# openSX70_MEROE_V7-5_20190606B.net
KiCad netlist of a schematic drawn in EAGLE
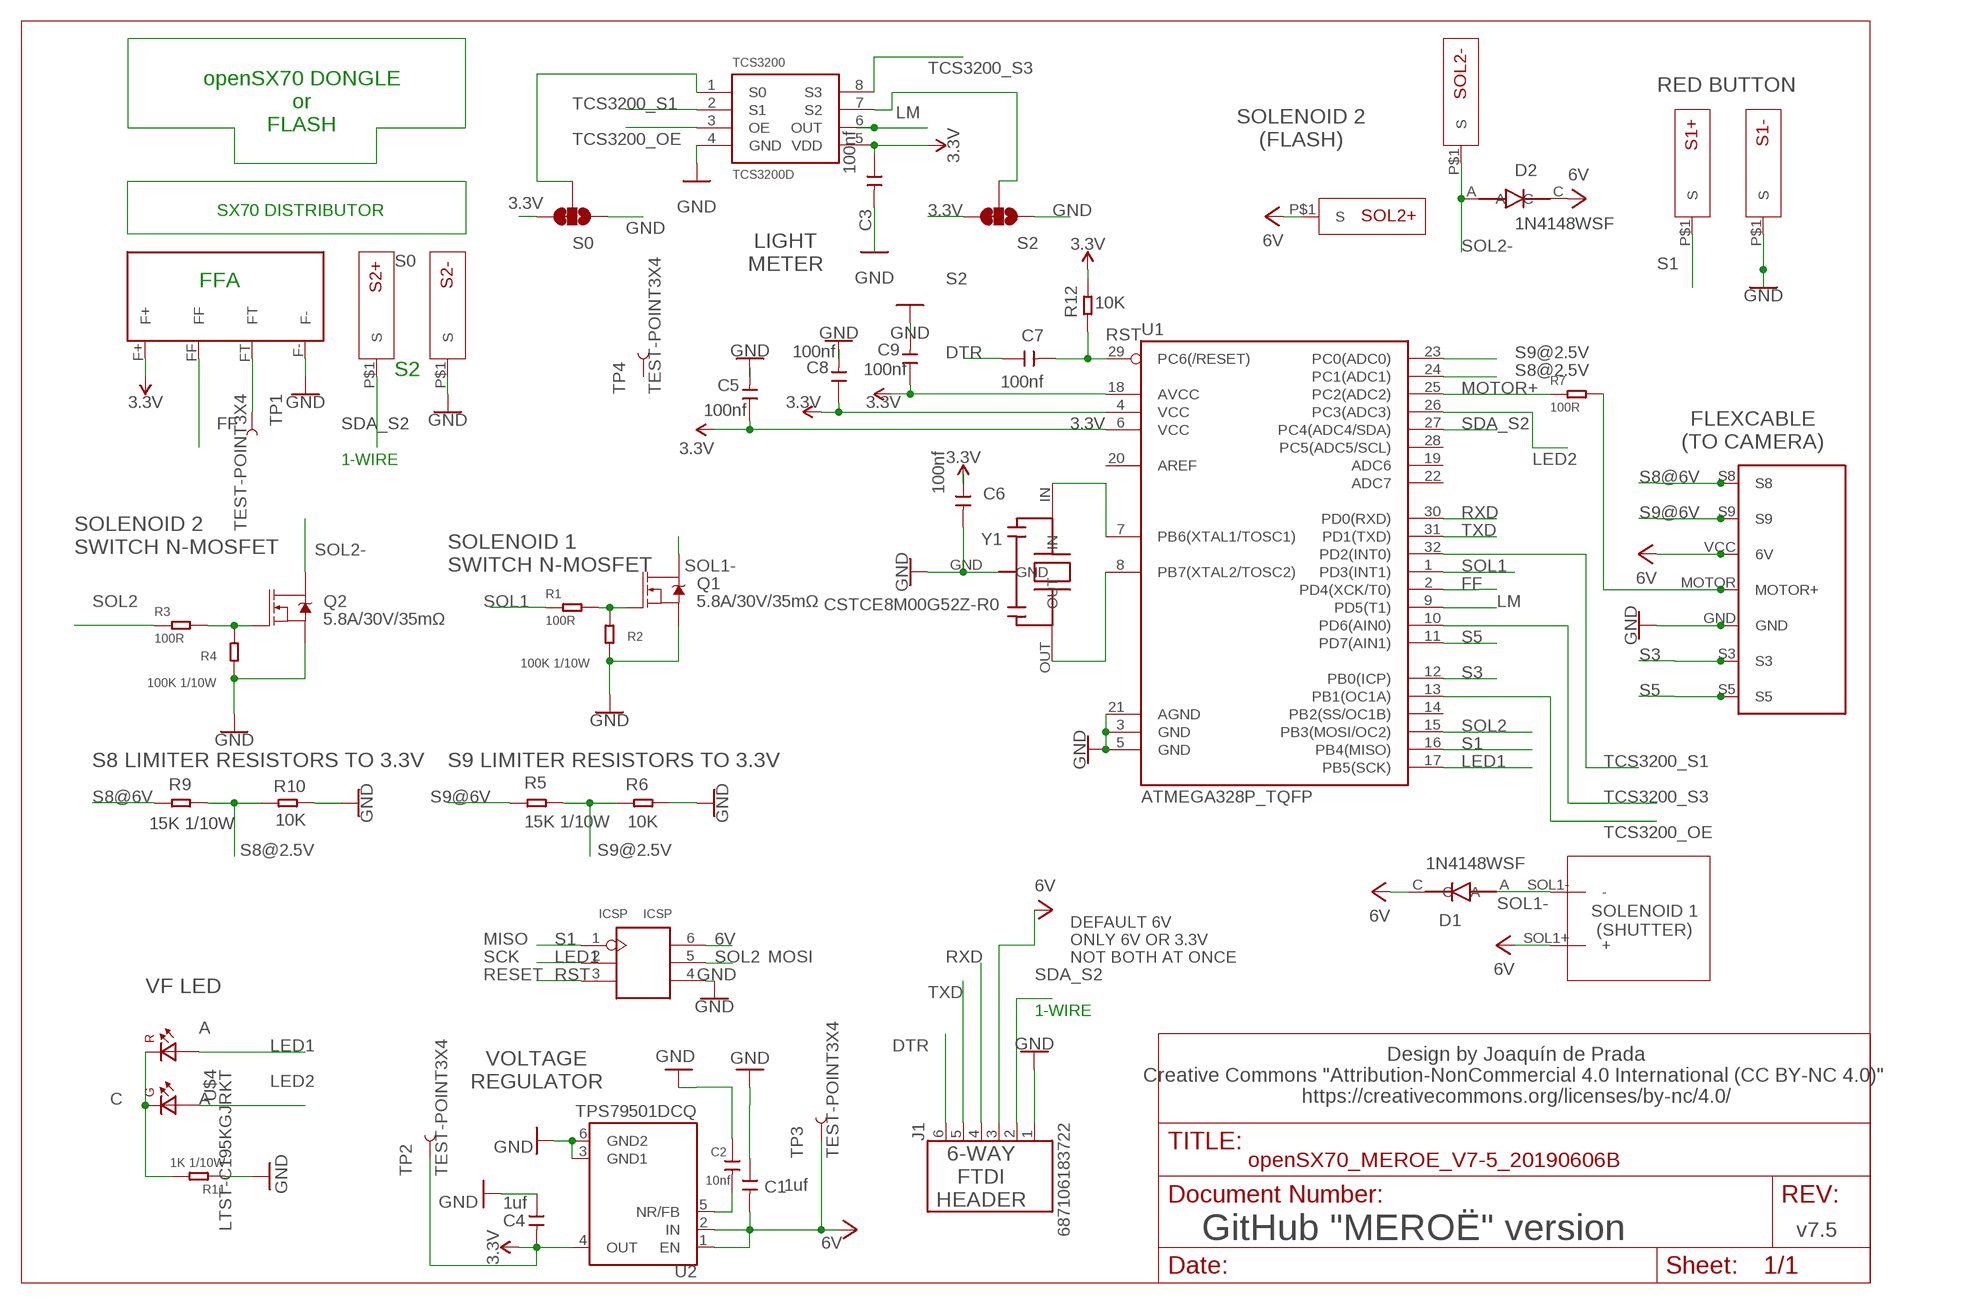
[diagram p0: schematic, sheet 1]

(export (version "E")
  (design (tool "Eeschema 10.0.6"))
  (components
    (comp (ref "C1")
      (value "1uf")
      (footprint "eagle-import:C0603")
      (fields (field (name "MPN") "CC0603KRX5R6BB106"))
      (libsource (lib "eagle-import") (part "CERAMIC-10UF-10V-10%-X5R(0603)"))
    )
    (comp (ref "C2")
      (value "10nf")
      (footprint "eagle-import:C0603")
      (fields (field (name "MPN") "CC0603KRX7R9BB104"))
      (libsource (lib "eagle-import") (part "CERAMIC-100NF-50V-10%-X7R(0603)"))
    )
    (comp (ref "C3")
      (value "100nf")
      (footprint "eagle-import:C0603")
      (fields (field (name "MPN") "CC0603KRX7R9BB104"))
      (libsource (lib "eagle-import") (part "CERAMIC-100NF-50V-10%-X7R(0603)"))
    )
    (comp (ref "C4")
      (value "1uf")
      (footprint "eagle-import:C0603")
      (fields (field (name "MPN") "CC0603KRX5R6BB106"))
      (libsource (lib "eagle-import") (part "CERAMIC-10UF-10V-10%-X5R(0603)"))
    )
    (comp (ref "C5")
      (value "100nf")
      (footprint "eagle-import:C0603")
      (fields (field (name "MPN") "CC0603KRX7R9BB104"))
      (libsource (lib "eagle-import") (part "CERAMIC-100NF-50V-10%-X7R(0603)"))
    )
    (comp (ref "C6")
      (value "100nf")
      (footprint "eagle-import:C0603")
      (fields (field (name "MPN") "CC0603KRX7R9BB104"))
      (libsource (lib "eagle-import") (part "CERAMIC-100NF-50V-10%-X7R(0603)"))
    )
    (comp (ref "C7")
      (value "100nf")
      (footprint "eagle-import:C0603")
      (fields (field (name "MPN") "CC0603KRX7R9BB104"))
      (libsource (lib "eagle-import") (part "CERAMIC-100NF-50V-10%-X7R(0603)"))
    )
    (comp (ref "C8")
      (value "100nf")
      (footprint "eagle-import:C0603")
      (fields (field (name "MPN") "CC0603KRX7R9BB104"))
      (libsource (lib "eagle-import") (part "CERAMIC-100NF-50V-10%-X7R(0603)"))
    )
    (comp (ref "C9")
      (value "100nf")
      (footprint "eagle-import:C0603")
      (fields (field (name "MPN") "CC0603KRX7R9BB104"))
      (libsource (lib "eagle-import") (part "CERAMIC-100NF-50V-10%-X7R(0603)"))
    )
    (comp (ref "D1")
      (value "1N4148WSF")
      (footprint "eagle-import:SODFL2512X100N")
      (fields (field (name "MANUFACTURER") "Fairchild Semiconductor"))
      (libsource (lib "eagle-import") (part "1N4148WS"))
    )
    (comp (ref "D2")
      (value "1N4148WSF")
      (footprint "eagle-import:SODFL2512X100N")
      (fields (field (name "MANUFACTURER") "Fairchild Semiconductor"))
      (libsource (lib "eagle-import") (part "1N4148WS"))
    )
    (comp (ref "ICSP")
      (value "ICSP")
      (footprint "eagle-import:H2X3-2.54")
      (libsource (lib "eagle-import") (part "ICSP"))
    )
    (comp (ref "J1")
      (value "687106183722")
      (footprint "eagle-import:687106183722")
      (fields (field (name "MF") "Wurth Electronics"))
      (libsource (lib "eagle-import") (part "687106183722"))
    )
    (comp (ref "Q1")
      (value "5.8A/30V/35mΩ")
      (footprint "eagle-import:SOT23-3")
      (libsource (lib "eagle-import") (part "MOSFET-NCH-AO3404A"))
    )
    (comp (ref "Q2")
      (value "5.8A/30V/35mΩ")
      (footprint "eagle-import:SOT23-3")
      (libsource (lib "eagle-import") (part "MOSFET-NCH-AO3404A"))
    )
    (comp (ref "R1")
      (value "100R")
      (footprint "eagle-import:R0603")
      (fields (field (name "MPN") "RC0603JR-07100RL"))
      (libsource (lib "eagle-import") (part "SMD-RES-100R-5%-1/10W(0603)"))
    )
    (comp (ref "R2")
      (value "100K 1/10W")
      (footprint "eagle-import:R0603")
      (fields (field (name "MPN") "RC0603JR-07100KL"))
      (libsource (lib "eagle-import") (part "SMD-RES-100K-5%-1/10W(0603)"))
    )
    (comp (ref "R3")
      (value "100R")
      (footprint "eagle-import:R0603")
      (fields (field (name "MPN") "RC0603JR-07100RL"))
      (libsource (lib "eagle-import") (part "SMD-RES-100R-5%-1/10W(0603)"))
    )
    (comp (ref "R4")
      (value "100K 1/10W")
      (footprint "eagle-import:R0603")
      (fields (field (name "MPN") "RC0603JR-07100KL"))
      (libsource (lib "eagle-import") (part "SMD-RES-100K-5%-1/10W(0603)"))
    )
    (comp (ref "R5")
      (value "15K 1/10W")
      (footprint "eagle-import:R0603")
      (fields (field (name "MPN") "RC0603FR-0715KL"))
      (libsource (lib "eagle-import") (part "SMD-RES-15K-1%-1/10W(0603)"))
    )
    (comp (ref "R6")
      (value "10K")
      (footprint "eagle-import:R0603")
      (fields (field (name "MPN") "RC0603FR-0710KL"))
      (libsource (lib "eagle-import") (part "SMD-RES-10K-1%-1/10W(0603)"))
    )
    (comp (ref "R7")
      (value "100R")
      (footprint "eagle-import:R0603")
      (fields (field (name "MPN") "RC0603JR-07100RL"))
      (libsource (lib "eagle-import") (part "SMD-RES-100R-5%-1/10W(0603)"))
    )
    (comp (ref "R9")
      (value "15K 1/10W")
      (footprint "eagle-import:R0603")
      (fields (field (name "MPN") "RC0603FR-0715KL"))
      (libsource (lib "eagle-import") (part "SMD-RES-15K-1%-1/10W(0603)"))
    )
    (comp (ref "R10")
      (value "10K")
      (footprint "eagle-import:R0603")
      (fields (field (name "MPN") "RC0603FR-0710KL"))
      (libsource (lib "eagle-import") (part "SMD-RES-10K-1%-1/10W(0603)"))
    )
    (comp (ref "R11")
      (value "1K 1/10W")
      (footprint "eagle-import:R0603")
      (fields (field (name "MPN") "RC0603JR-071KL"))
      (libsource (lib "eagle-import") (part "SMD-RES-1K-5%-1/10W(0603)"))
    )
    (comp (ref "R12")
      (value "10K")
      (footprint "eagle-import:R0603")
      (fields (field (name "MPN") "RC0603FR-0710KL"))
      (libsource (lib "eagle-import") (part "SMD-RES-10K-1%-1/10W(0603)"))
    )
    (comp (ref "S0")
      (value "S0")
      (footprint "eagle-import:SMT-JUMPER_3_1-NC_TRACE_SILK")
      (libsource (lib "eagle-import") (part "JUMPER-SMT_3_1-NC_TRACE_SILK"))
    )
    (comp (ref "S1+")
      (value "SX70-S-PAD-NEW")
      (footprint "eagle-import:SX70-S-PAD2")
      (libsource (lib "eagle-import") (part "SX70-S-PAD-NEW"))
    )
    (comp (ref "S1-")
      (value "SX70-S-PAD-NEW")
      (footprint "eagle-import:SX70-S-PAD2")
      (libsource (lib "eagle-import") (part "SX70-S-PAD-NEW"))
    )
    (comp (ref "S2")
      (value "S2")
      (footprint "eagle-import:SMT-JUMPER_3_1-NC_TRACE_SILK")
      (libsource (lib "eagle-import") (part "JUMPER-SMT_3_1-NC_TRACE_SILK"))
    )
    (comp (ref "S2+")
      (value "SX70-S-PAD-NEW")
      (footprint "eagle-import:SX70-S-PAD2")
      (libsource (lib "eagle-import") (part "SX70-S-PAD-NEW"))
    )
    (comp (ref "S2-")
      (value "SX70-S-PAD-NEW")
      (footprint "eagle-import:SX70-S-PAD2")
      (libsource (lib "eagle-import") (part "SX70-S-PAD-NEW"))
    )
    (comp (ref "SOL1")
      (value "SX70-SOLENOID1-2PADS")
      (footprint "eagle-import:SX70-SOLENOID1-2")
      (libsource (lib "eagle-import") (part "SX70-SOLENOID1-2PADS"))
    )
    (comp (ref "SOL2+")
      (value "SX70-S-PAD-NEW")
      (footprint "eagle-import:SX70-S-PAD2")
      (libsource (lib "eagle-import") (part "SX70-S-PAD-NEW"))
    )
    (comp (ref "SOL2-")
      (value "SX70-S-PAD-NEW")
      (footprint "eagle-import:SX70-S-PAD2")
      (libsource (lib "eagle-import") (part "SX70-S-PAD-NEW"))
    )
    (comp (ref "TCS3200")
      (value "TCS3200D")
      (footprint "eagle-import:SOIC8")
      (fields (field (name "MF") "ams") (field (name "MP") "TCS3200D-TR"))
      (libsource (lib "eagle-import") (part "TCS3200D"))
    )
    (comp (ref "TP1")
      (value "TEST-POINT3X4")
      (footprint "eagle-import:PAD.03X.04")
      (libsource (lib "eagle-import") (part "TEST-POINT3X4"))
    )
    (comp (ref "TP2")
      (value "TEST-POINT3X4")
      (footprint "eagle-import:PAD.03X.04")
      (libsource (lib "eagle-import") (part "TEST-POINT3X4"))
    )
    (comp (ref "TP3")
      (value "TEST-POINT3X4")
      (footprint "eagle-import:PAD.03X.04")
      (libsource (lib "eagle-import") (part "TEST-POINT3X4"))
    )
    (comp (ref "TP4")
      (value "TEST-POINT3X4")
      (footprint "eagle-import:PAD.03X.04")
      (libsource (lib "eagle-import") (part "TEST-POINT3X4"))
    )
    (comp (ref "U$1")
      (value "SX70-7-PAD")
      (footprint "eagle-import:SX70-7-PAD-PROPER")
      (libsource (lib "eagle-import") (part "SX70-7-PAD"))
    )
    (comp (ref "U$2")
      (value "FFA")
      (footprint "eagle-import:FFA-PAD-PACKAGE")
      (libsource (lib "eagle-import") (part "SX70-FFA-PAD"))
    )
    (comp (ref "U$4")
      (value "LTST-C195KGJRKT")
      (footprint "eagle-import:LTST-BILED-15X16")
      (fields (field (name "MF") "Lite-On Inc."))
      (libsource (lib "eagle-import") (part "LTST-C195KGJRKT"))
    )
    (comp (ref "U1")
      (value "ATMEGA328P_TQFP")
      (footprint "eagle-import:TQFP32-08")
      (libsource (lib "eagle-import") (part "ATMEGA328P_TQFP"))
    )
    (comp (ref "U2")
      (value "TPS79501DCQ")
      (footprint "eagle-import:SOT127P706X180-6N")
      (fields (field (name "MF") "Texas Instruments"))
      (libsource (lib "eagle-import") (part "TPS79501DCQ"))
    )
    (comp (ref "Y1")
      (value "CSTCE8M00G52Z-R0")
      (footprint "eagle-import:CFP95P160X100-3N")
      (fields (field (name "MF") "Murata") (field (name "MP") "CSTCE16M0V53-R0"))
      (libsource (lib "eagle-import") (part "CSTCE16M0V53-R0"))
    )
  )
  (nets
    (net (code "1") (name "/DTR") (class "Default")
      (node (ref "C7") (pin "1") (pinfunction "1_1") (pintype "passive"))
      (node (ref "J1") (pin "6") (pinfunction "1_6") (pintype "passive"))
    )
    (net (code "2") (name "/FF") (class "Default")
      (node (ref "U$2") (pin "FF") (pinfunction "FF_FF") (pintype "bidirectional"))
      (node (ref "U1") (pin "2") (pinfunction "PD4(XCK/T0)_2") (pintype "bidirectional"))
    )
    (net (code "3") (name "/LED1") (class "Default")
      (node (ref "ICSP") (pin "2") (pinfunction "SCK_2") (pintype "bidirectional"))
      (node (ref "U$4") (pin "P$2") (pinfunction "A2_P$2") (pintype "passive"))
      (node (ref "U1") (pin "17") (pinfunction "PB5(SCK)_17") (pintype "bidirectional"))
    )
    (net (code "4") (name "/LED2") (class "Default")
      (node (ref "U$4") (pin "P$1") (pinfunction "A1_P$1") (pintype "passive"))
      (node (ref "U1") (pin "26") (pinfunction "PC3(ADC3)_26") (pintype "bidirectional"))
    )
    (net (code "5") (name "/LM") (class "Default")
      (node (ref "TCS3200") (pin "6") (pinfunction "OUT_6") (pintype "bidirectional"))
      (node (ref "U1") (pin "9") (pinfunction "PD5(T1)_9") (pintype "bidirectional"))
    )
    (net (code "6") (name "/MOTOR+") (class "Default")
      (node (ref "R7") (pin "1") (pinfunction "1_1") (pintype "passive"))
      (node (ref "U1") (pin "25") (pinfunction "PC2(ADC2)_25") (pintype "bidirectional"))
    )
    (net (code "7") (name "/RST") (class "Default")
      (node (ref "C7") (pin "2") (pinfunction "2_2") (pintype "passive"))
      (node (ref "ICSP") (pin "3") (pinfunction "RST_3") (pintype "bidirectional"))
      (node (ref "R12") (pin "1") (pinfunction "1_1") (pintype "passive"))
      (node (ref "U1") (pin "29") (pinfunction "PC6(/RESET)_29") (pintype "bidirectional"))
    )
    (net (code "8") (name "/RXD") (class "Default")
      (node (ref "J1") (pin "4") (pinfunction "3_4") (pintype "passive"))
      (node (ref "U1") (pin "30") (pinfunction "PD0(RXD)_30") (pintype "bidirectional"))
    )
    (net (code "9") (name "/S1") (class "Default")
      (node (ref "ICSP") (pin "1") (pinfunction "MISO_1") (pintype "bidirectional"))
      (node (ref "S1+") (pin "P$1") (pinfunction "S_P$1") (pintype "bidirectional"))
      (node (ref "U1") (pin "16") (pinfunction "PB4(MISO)_16") (pintype "bidirectional"))
    )
    (net (code "10") (name "/S3") (class "Default")
      (node (ref "U$1") (pin "S3") (pinfunction "S3_S3") (pintype "bidirectional"))
      (node (ref "U1") (pin "12") (pinfunction "PB0(ICP)_12") (pintype "bidirectional"))
    )
    (net (code "11") (name "/S5") (class "Default")
      (node (ref "U$1") (pin "S5") (pinfunction "S5_S5") (pintype "bidirectional"))
      (node (ref "U1") (pin "11") (pinfunction "PD7(AIN1)_11") (pintype "bidirectional"))
    )
    (net (code "12") (name "/S8@2.5V") (class "Default")
      (node (ref "R10") (pin "1") (pinfunction "1_1") (pintype "passive"))
      (node (ref "R9") (pin "2") (pinfunction "2_2") (pintype "passive"))
      (node (ref "U1") (pin "24") (pinfunction "PC1(ADC1)_24") (pintype "bidirectional"))
    )
    (net (code "13") (name "/S8@6V") (class "Default")
      (node (ref "R9") (pin "1") (pinfunction "1_1") (pintype "passive"))
      (node (ref "U$1") (pin "S8") (pinfunction "S8_S8") (pintype "bidirectional"))
    )
    (net (code "14") (name "/S9@2.5V") (class "Default")
      (node (ref "R5") (pin "2") (pinfunction "2_2") (pintype "passive"))
      (node (ref "R6") (pin "1") (pinfunction "1_1") (pintype "passive"))
      (node (ref "U1") (pin "23") (pinfunction "PC0(ADC0)_23") (pintype "bidirectional"))
    )
    (net (code "15") (name "/S9@6V") (class "Default")
      (node (ref "R5") (pin "1") (pinfunction "1_1") (pintype "passive"))
      (node (ref "U$1") (pin "S9") (pinfunction "S9_S9") (pintype "bidirectional"))
    )
    (net (code "16") (name "/SDA_S2") (class "Default")
      (node (ref "J1") (pin "2") (pinfunction "5_2") (pintype "passive"))
      (node (ref "S2+") (pin "P$1") (pinfunction "S_P$1") (pintype "bidirectional"))
      (node (ref "U1") (pin "27") (pinfunction "PC4(ADC4/SDA)_27") (pintype "bidirectional"))
    )
    (net (code "17") (name "/SOL1") (class "Default")
      (node (ref "R1") (pin "1") (pinfunction "1_1") (pintype "passive"))
      (node (ref "U1") (pin "1") (pinfunction "PD3(INT1)_1") (pintype "bidirectional"))
    )
    (net (code "18") (name "/SOL1-") (class "Default")
      (node (ref "D1") (pin "A") (pinfunction "A_A") (pintype "passive"))
      (node (ref "Q1") (pin "3") (pinfunction "D_3") (pintype "bidirectional"))
      (node (ref "SOL1") (pin "SOL1-") (pinfunction "-_SOL1-") (pintype "bidirectional"))
    )
    (net (code "19") (name "/SOL2") (class "Default")
      (node (ref "ICSP") (pin "5") (pinfunction "MOSI_5") (pintype "bidirectional"))
      (node (ref "R3") (pin "1") (pinfunction "1_1") (pintype "passive"))
      (node (ref "U1") (pin "15") (pinfunction "PB3(MOSI/OC2)_15") (pintype "bidirectional"))
    )
    (net (code "20") (name "/SOL2-") (class "Default")
      (node (ref "D2") (pin "A") (pinfunction "A_A") (pintype "passive"))
      (node (ref "Q2") (pin "3") (pinfunction "D_3") (pintype "bidirectional"))
      (node (ref "SOL2-") (pin "P$1") (pinfunction "S_P$1") (pintype "bidirectional"))
    )
    (net (code "21") (name "/TCS3200_OE") (class "Default")
      (node (ref "TCS3200") (pin "3") (pinfunction "OE_3") (pintype "bidirectional"))
      (node (ref "U1") (pin "13") (pinfunction "PB1(OC1A)_13") (pintype "bidirectional"))
    )
    (net (code "22") (name "/TCS3200_S1") (class "Default")
      (node (ref "TCS3200") (pin "2") (pinfunction "S1_2") (pintype "bidirectional"))
      (node (ref "U1") (pin "32") (pinfunction "PD2(INT0)_32") (pintype "bidirectional"))
    )
    (net (code "23") (name "/TCS3200_S3") (class "Default")
      (node (ref "TCS3200") (pin "8") (pinfunction "S3_8") (pintype "bidirectional"))
      (node (ref "U1") (pin "10") (pinfunction "PD6(AIN0)_10") (pintype "bidirectional"))
    )
    (net (code "24") (name "/TXD") (class "Default")
      (node (ref "J1") (pin "5") (pinfunction "2_5") (pintype "passive"))
      (node (ref "U1") (pin "31") (pinfunction "PD1(TXD)_31") (pintype "bidirectional"))
    )
    (net (code "25") (name "3.3V") (class "Default")
      (node (ref "C3") (pin "1") (pinfunction "1_1") (pintype "passive"))
      (node (ref "C4") (pin "2") (pinfunction "2_2") (pintype "passive"))
      (node (ref "C5") (pin "1") (pinfunction "1_1") (pintype "passive"))
      (node (ref "C6") (pin "1") (pinfunction "1_1") (pintype "passive"))
      (node (ref "C8") (pin "1") (pinfunction "1_1") (pintype "passive"))
      (node (ref "C9") (pin "1") (pinfunction "1_1") (pintype "passive"))
      (node (ref "R12") (pin "2") (pinfunction "2_2") (pintype "passive"))
      (node (ref "S0") (pin "3") (pinfunction "3_3") (pintype "passive"))
      (node (ref "S2") (pin "3") (pinfunction "3_3") (pintype "passive"))
      (node (ref "TCS3200") (pin "5") (pinfunction "VDD_5") (pintype "bidirectional"))
      (node (ref "TP2") (pin "P$1") (pinfunction "1_P$1") (pintype "bidirectional"))
      (node (ref "U$2") (pin "F+") (pinfunction "F+_F+") (pintype "bidirectional"))
      (node (ref "U1") (pin "18") (pinfunction "AVCC_18") (pintype "bidirectional"))
      (node (ref "U1") (pin "4") (pinfunction "VCC_4") (pintype "bidirectional"))
      (node (ref "U1") (pin "6") (pinfunction "VCC_6") (pintype "bidirectional"))
      (node (ref "U2") (pin "4") (pinfunction "OUT_4") (pintype "output"))
    )
    (net (code "26") (name "6V") (class "Default")
      (node (ref "C1") (pin "2") (pinfunction "2_2") (pintype "passive"))
      (node (ref "D1") (pin "C") (pinfunction "C_C") (pintype "passive"))
      (node (ref "D2") (pin "C") (pinfunction "C_C") (pintype "passive"))
      (node (ref "ICSP") (pin "6") (pinfunction "VCC_6") (pintype "bidirectional"))
      (node (ref "J1") (pin "3") (pinfunction "4_3") (pintype "passive"))
      (node (ref "SOL1") (pin "SOL1+") (pinfunction "+_SOL1+") (pintype "bidirectional"))
      (node (ref "SOL2+") (pin "P$1") (pinfunction "S_P$1") (pintype "bidirectional"))
      (node (ref "TP3") (pin "P$1") (pinfunction "1_P$1") (pintype "bidirectional"))
      (node (ref "U$1") (pin "VCC") (pinfunction "6V_VCC") (pintype "bidirectional"))
      (node (ref "U2") (pin "1") (pinfunction "EN_1") (pintype "input"))
      (node (ref "U2") (pin "2") (pinfunction "IN_2") (pintype "input"))
    )
    (net (code "27") (name "GND") (class "Default")
      (node (ref "C1") (pin "1") (pinfunction "1_1") (pintype "passive"))
      (node (ref "C2") (pin "1") (pinfunction "1_1") (pintype "passive"))
      (node (ref "C3") (pin "2") (pinfunction "2_2") (pintype "passive"))
      (node (ref "C4") (pin "1") (pinfunction "1_1") (pintype "passive"))
      (node (ref "C5") (pin "2") (pinfunction "2_2") (pintype "passive"))
      (node (ref "C6") (pin "2") (pinfunction "2_2") (pintype "passive"))
      (node (ref "C8") (pin "2") (pinfunction "2_2") (pintype "passive"))
      (node (ref "C9") (pin "2") (pinfunction "2_2") (pintype "passive"))
      (node (ref "ICSP") (pin "4") (pinfunction "GND_4") (pintype "bidirectional"))
      (node (ref "J1") (pin "1") (pinfunction "6_1") (pintype "passive"))
      (node (ref "Q1") (pin "2") (pinfunction "S_2") (pintype "bidirectional"))
      (node (ref "Q2") (pin "2") (pinfunction "S_2") (pintype "bidirectional"))
      (node (ref "R10") (pin "2") (pinfunction "2_2") (pintype "passive"))
      (node (ref "R11") (pin "1") (pinfunction "1_1") (pintype "passive"))
      (node (ref "R2") (pin "1") (pinfunction "1_1") (pintype "passive"))
      (node (ref "R4") (pin "1") (pinfunction "1_1") (pintype "passive"))
      (node (ref "R6") (pin "2") (pinfunction "2_2") (pintype "passive"))
      (node (ref "S0") (pin "1") (pinfunction "1_1") (pintype "passive"))
      (node (ref "S1-") (pin "P$1") (pinfunction "S_P$1") (pintype "bidirectional"))
      (node (ref "S2") (pin "1") (pinfunction "1_1") (pintype "passive"))
      (node (ref "S2-") (pin "P$1") (pinfunction "S_P$1") (pintype "bidirectional"))
      (node (ref "TCS3200") (pin "4") (pinfunction "GND_4") (pintype "bidirectional"))
      (node (ref "U$1") (pin "GND") (pinfunction "GND_GND") (pintype "bidirectional"))
      (node (ref "U$2") (pin "F-") (pinfunction "F-_F-") (pintype "bidirectional"))
      (node (ref "U1") (pin "21") (pinfunction "AGND_21") (pintype "bidirectional"))
      (node (ref "U1") (pin "3") (pinfunction "GND_3") (pintype "bidirectional"))
      (node (ref "U1") (pin "5") (pinfunction "GND_5") (pintype "bidirectional"))
      (node (ref "U2") (pin "3") (pinfunction "GND1_3") (pintype "power_in"))
      (node (ref "U2") (pin "6") (pinfunction "GND2_6") (pintype "power_in"))
      (node (ref "Y1") (pin "GND") (pinfunction "GND_GND") (pintype "passive"))
    )
    (net (code "28") (name "Net-(Q1-G)") (class "Default")
      (node (ref "Q1") (pin "1") (pinfunction "G_1") (pintype "bidirectional"))
      (node (ref "R1") (pin "2") (pinfunction "2_2") (pintype "passive"))
      (node (ref "R2") (pin "2") (pinfunction "2_2") (pintype "passive"))
    )
    (net (code "29") (name "Net-(Q2-G)") (class "Default")
      (node (ref "Q2") (pin "1") (pinfunction "G_1") (pintype "bidirectional"))
      (node (ref "R3") (pin "2") (pinfunction "2_2") (pintype "passive"))
      (node (ref "R4") (pin "2") (pinfunction "2_2") (pintype "passive"))
    )
    (net (code "30") (name "Net-(TCS3200-S0)") (class "Default")
      (node (ref "S0") (pin "2") (pinfunction "2_2") (pintype "passive"))
      (node (ref "TCS3200") (pin "1") (pinfunction "S0_1") (pintype "bidirectional"))
    )
    (net (code "31") (name "Net-(TCS3200-S2)") (class "Default")
      (node (ref "S2") (pin "2") (pinfunction "2_2") (pintype "passive"))
      (node (ref "TCS3200") (pin "7") (pinfunction "S2_7") (pintype "bidirectional"))
    )
    (net (code "32") (name "Net-(TP1-1)") (class "Default")
      (node (ref "TP1") (pin "P$1") (pinfunction "1_P$1") (pintype "bidirectional"))
      (node (ref "U$2") (pin "FT") (pinfunction "FT_FT") (pintype "bidirectional"))
    )
    (net (code "33") (name "Net-(U$1-MOTOR+)") (class "Default")
      (node (ref "R7") (pin "2") (pinfunction "2_2") (pintype "passive"))
      (node (ref "U$1") (pin "MOTOR") (pinfunction "MOTOR+_MOTOR") (pintype "bidirectional"))
    )
    (net (code "34") (name "Net-(U$4-K1)") (class "Default")
      (node (ref "R11") (pin "2") (pinfunction "2_2") (pintype "passive"))
      (node (ref "U$4") (pin "P$3") (pinfunction "K1_P$3") (pintype "passive"))
      (node (ref "U$4") (pin "P$4") (pinfunction "K2_P$4") (pintype "passive"))
    )
    (net (code "35") (name "Net-(U1-PB6(XTAL1{slash}TOSC1))") (class "Default")
      (node (ref "U1") (pin "7") (pinfunction "PB6(XTAL1/TOSC1)_7") (pintype "bidirectional"))
      (node (ref "Y1") (pin "IN") (pinfunction "IN_IN") (pintype "input"))
    )
    (net (code "36") (name "Net-(U1-PB7(XTAL2{slash}TOSC2))") (class "Default")
      (node (ref "U1") (pin "8") (pinfunction "PB7(XTAL2/TOSC2)_8") (pintype "bidirectional"))
      (node (ref "Y1") (pin "OUT") (pinfunction "OUT_OUT") (pintype "output"))
    )
    (net (code "37") (name "Net-(U2-NR{slash}FB)") (class "Default")
      (node (ref "C2") (pin "2") (pinfunction "2_2") (pintype "passive"))
      (node (ref "U2") (pin "5") (pinfunction "NR/FB_5") (pintype "input"))
    )
    (net (code "38") (name "unconnected-(TP4-1-PadP$1)") (class "Default")
      (node (ref "TP4") (pin "P$1") (pinfunction "1_P$1") (pintype "bidirectional"))
    )
    (net (code "39") (name "unconnected-(U1-ADC6-Pad19)") (class "Default")
      (node (ref "U1") (pin "19") (pinfunction "ADC6_19") (pintype "bidirectional"))
    )
    (net (code "40") (name "unconnected-(U1-ADC7-Pad22)") (class "Default")
      (node (ref "U1") (pin "22") (pinfunction "ADC7_22") (pintype "bidirectional"))
    )
    (net (code "41") (name "unconnected-(U1-AREF-Pad20)") (class "Default")
      (node (ref "U1") (pin "20") (pinfunction "AREF_20") (pintype "bidirectional"))
    )
    (net (code "42") (name "unconnected-(U1-PB2(SS{slash}OC1B)-Pad14)") (class "Default")
      (node (ref "U1") (pin "14") (pinfunction "PB2(SS/OC1B)_14") (pintype "bidirectional"))
    )
    (net (code "43") (name "unconnected-(U1-PC5(ADC5{slash}SCL)-Pad28)") (class "Default")
      (node (ref "U1") (pin "28") (pinfunction "PC5(ADC5/SCL)_28") (pintype "bidirectional"))
    )
  )
)
